# Servorino_FT230X_prototype.net
KiCad netlist of a schematic drawn in EAGLE
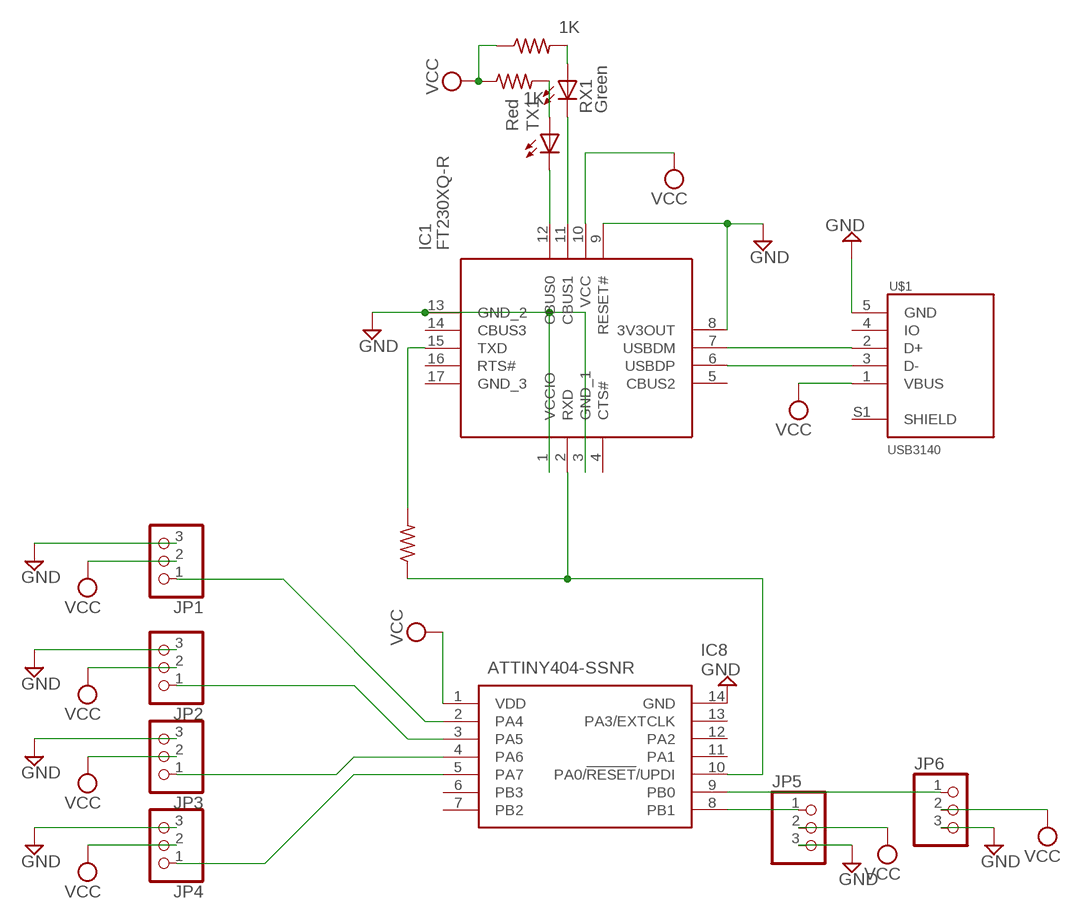
[diagram p0: schematic, sheet 1]

(export (version "E")
  (design (tool "Eeschema 10.0.6"))
  (components
    (comp (ref "IC1")
      (value "FT230XQ-R")
      (footprint "eagle-import:QFN65P400X400X80-17N")
      (fields (field (name "MOUSER_PART_NUMBER") "895-FT230XQ-R"))
      (libsource (lib "eagle-import") (part "FT230XQ-R"))
    )
    (comp (ref "IC8")
      (value "ATTINY404-SSNR")
      (footprint "eagle-import:SOIC127P600X175-14N")
      (fields (field (name "MOUSER_PART_NUMBER") "556-ATTINY404-SSNR"))
      (libsource (lib "eagle-import") (part "ATTINY404-SSNR"))
    )
    (comp (ref "JP1")
      (value "PINHD-1X3")
      (footprint "eagle-import:1X03")
      (libsource (lib "eagle-import") (part "PINHD-1X3"))
    )
    (comp (ref "JP2")
      (value "PINHD-1X3")
      (footprint "eagle-import:1X03")
      (libsource (lib "eagle-import") (part "PINHD-1X3"))
    )
    (comp (ref "JP3")
      (value "PINHD-1X3")
      (footprint "eagle-import:1X03")
      (libsource (lib "eagle-import") (part "PINHD-1X3"))
    )
    (comp (ref "JP4")
      (value "PINHD-1X3")
      (footprint "eagle-import:1X03")
      (libsource (lib "eagle-import") (part "PINHD-1X3"))
    )
    (comp (ref "JP5")
      (value "PINHD-1X3")
      (footprint "eagle-import:1X03")
      (libsource (lib "eagle-import") (part "PINHD-1X3"))
    )
    (comp (ref "JP6")
      (value "PINHD-1X3")
      (footprint "eagle-import:1X03")
      (libsource (lib "eagle-import") (part "PINHD-1X3"))
    )
    (comp (ref "R4")
      (value "1K")
      (footprint "eagle-import:R0805")
      (libsource (lib "eagle-import") (part "R-US_R0805"))
    )
    (comp (ref "R5")
      (value "1K")
      (footprint "eagle-import:R0805")
      (libsource (lib "eagle-import") (part "R-US_R0805"))
    )
    (comp (ref "R6")
      (value "470")
      (footprint "eagle-import:R0805")
      (libsource (lib "eagle-import") (part "R-US_R0805"))
    )
    (comp (ref "RX1")
      (value "Green")
      (footprint "eagle-import:CHIP-LED0805")
      (libsource (lib "eagle-import") (part "LEDCHIP-LED0805"))
    )
    (comp (ref "TX1")
      (value "Red")
      (footprint "eagle-import:CHIP-LED0805")
      (libsource (lib "eagle-import") (part "LEDCHIP-LED0805"))
    )
    (comp (ref "U$1")
      (value "USB3140")
      (footprint "eagle-import:USB3140-30-0170-0-C")
      (libsource (lib "eagle-import") (part "USB3140"))
    )
  )
  (nets
    (net (code "1") (name "GND") (class "Default")
      (node (ref "IC1") (pin "1") (pinfunction "VCCIO_1") (pintype "bidirectional"))
      (node (ref "IC1") (pin "13") (pinfunction "GND_2_13") (pintype "bidirectional"))
      (node (ref "IC1") (pin "3") (pinfunction "GND_1_3") (pintype "bidirectional"))
      (node (ref "IC1") (pin "8") (pinfunction "3V3OUT_8") (pintype "bidirectional"))
      (node (ref "IC1") (pin "9") (pinfunction "RESET#_9") (pintype "bidirectional"))
      (node (ref "IC8") (pin "14") (pinfunction "GND_14") (pintype "bidirectional"))
      (node (ref "JP1") (pin "3") (pinfunction "3_3") (pintype "passive"))
      (node (ref "JP2") (pin "3") (pinfunction "3_3") (pintype "passive"))
      (node (ref "JP3") (pin "3") (pinfunction "3_3") (pintype "passive"))
      (node (ref "JP4") (pin "3") (pinfunction "3_3") (pintype "passive"))
      (node (ref "JP5") (pin "3") (pinfunction "3_3") (pintype "passive"))
      (node (ref "JP6") (pin "3") (pinfunction "3_3") (pintype "passive"))
      (node (ref "U$1") (pin "5") (pinfunction "GND_5") (pintype "passive"))
    )
    (net (code "2") (name "Net-(IC1-CBUS0)") (class "Default")
      (node (ref "IC1") (pin "12") (pinfunction "CBUS0_12") (pintype "bidirectional"))
      (node (ref "TX1") (pin "C") (pinfunction "C_C") (pintype "passive"))
    )
    (net (code "3") (name "Net-(IC1-CBUS1)") (class "Default")
      (node (ref "IC1") (pin "11") (pinfunction "CBUS1_11") (pintype "bidirectional"))
      (node (ref "RX1") (pin "C") (pinfunction "C_C") (pintype "passive"))
    )
    (net (code "4") (name "Net-(IC1-RXD)") (class "Default")
      (node (ref "IC1") (pin "2") (pinfunction "RXD_2") (pintype "bidirectional"))
      (node (ref "IC8") (pin "10") (pinfunction "PA0/~{RESET}/UPDI_10") (pintype "bidirectional"))
      (node (ref "R6") (pin "1") (pinfunction "1_1") (pintype "passive"))
    )
    (net (code "5") (name "Net-(IC1-TXD)") (class "Default")
      (node (ref "IC1") (pin "15") (pinfunction "TXD_15") (pintype "bidirectional"))
      (node (ref "R6") (pin "2") (pinfunction "2_2") (pintype "passive"))
    )
    (net (code "6") (name "Net-(IC1-USBDM)") (class "Default")
      (node (ref "IC1") (pin "7") (pinfunction "USBDM_7") (pintype "bidirectional"))
      (node (ref "U$1") (pin "2") (pinfunction "D+_2") (pintype "passive"))
    )
    (net (code "7") (name "Net-(IC1-USBDP)") (class "Default")
      (node (ref "IC1") (pin "6") (pinfunction "USBDP_6") (pintype "bidirectional"))
      (node (ref "U$1") (pin "3") (pinfunction "D-_3") (pintype "passive"))
    )
    (net (code "8") (name "Net-(IC8-PA4)") (class "Default")
      (node (ref "IC8") (pin "2") (pinfunction "PA4_2") (pintype "bidirectional"))
      (node (ref "JP1") (pin "1") (pinfunction "1_1") (pintype "passive"))
    )
    (net (code "9") (name "Net-(IC8-PA5)") (class "Default")
      (node (ref "IC8") (pin "3") (pinfunction "PA5_3") (pintype "bidirectional"))
      (node (ref "JP2") (pin "1") (pinfunction "1_1") (pintype "passive"))
    )
    (net (code "10") (name "Net-(IC8-PA6)") (class "Default")
      (node (ref "IC8") (pin "4") (pinfunction "PA6_4") (pintype "bidirectional"))
      (node (ref "JP3") (pin "1") (pinfunction "1_1") (pintype "passive"))
    )
    (net (code "11") (name "Net-(IC8-PA7)") (class "Default")
      (node (ref "IC8") (pin "5") (pinfunction "PA7_5") (pintype "bidirectional"))
      (node (ref "JP4") (pin "1") (pinfunction "1_1") (pintype "passive"))
    )
    (net (code "12") (name "Net-(IC8-PB0)") (class "Default")
      (node (ref "IC8") (pin "9") (pinfunction "PB0_9") (pintype "bidirectional"))
      (node (ref "JP6") (pin "1") (pinfunction "1_1") (pintype "passive"))
    )
    (net (code "13") (name "Net-(IC8-PB1)") (class "Default")
      (node (ref "IC8") (pin "8") (pinfunction "PB1_8") (pintype "bidirectional"))
      (node (ref "JP5") (pin "1") (pinfunction "1_1") (pintype "passive"))
    )
    (net (code "14") (name "Net-(R4-Pad2)") (class "Default")
      (node (ref "R4") (pin "2") (pinfunction "2_2") (pintype "passive"))
      (node (ref "RX1") (pin "A") (pinfunction "A_A") (pintype "passive"))
    )
    (net (code "15") (name "Net-(R5-Pad2)") (class "Default")
      (node (ref "R5") (pin "2") (pinfunction "2_2") (pintype "passive"))
      (node (ref "TX1") (pin "A") (pinfunction "A_A") (pintype "passive"))
    )
    (net (code "16") (name "VCC") (class "Default")
      (node (ref "IC1") (pin "10") (pinfunction "VCC_10") (pintype "bidirectional"))
      (node (ref "IC8") (pin "1") (pinfunction "VDD_1") (pintype "bidirectional"))
      (node (ref "JP1") (pin "2") (pinfunction "2_2") (pintype "passive"))
      (node (ref "JP2") (pin "2") (pinfunction "2_2") (pintype "passive"))
      (node (ref "JP3") (pin "2") (pinfunction "2_2") (pintype "passive"))
      (node (ref "JP4") (pin "2") (pinfunction "2_2") (pintype "passive"))
      (node (ref "JP5") (pin "2") (pinfunction "2_2") (pintype "passive"))
      (node (ref "JP6") (pin "2") (pinfunction "2_2") (pintype "passive"))
      (node (ref "R4") (pin "1") (pinfunction "1_1") (pintype "passive"))
      (node (ref "R5") (pin "1") (pinfunction "1_1") (pintype "passive"))
      (node (ref "U$1") (pin "1") (pinfunction "VBUS_1") (pintype "passive"))
    )
    (net (code "17") (name "unconnected-(IC1-CBUS2-Pad5)") (class "Default")
      (node (ref "IC1") (pin "5") (pinfunction "CBUS2_5") (pintype "bidirectional"))
    )
    (net (code "18") (name "unconnected-(IC1-CBUS3-Pad14)") (class "Default")
      (node (ref "IC1") (pin "14") (pinfunction "CBUS3_14") (pintype "bidirectional"))
    )
    (net (code "19") (name "unconnected-(IC1-CTS#-Pad4)") (class "Default")
      (node (ref "IC1") (pin "4") (pinfunction "CTS#_4") (pintype "bidirectional"))
    )
    (net (code "20") (name "unconnected-(IC1-GND_3-Pad17)") (class "Default")
      (node (ref "IC1") (pin "17") (pinfunction "GND_3_17") (pintype "bidirectional"))
    )
    (net (code "21") (name "unconnected-(IC1-RTS#-Pad16)") (class "Default")
      (node (ref "IC1") (pin "16") (pinfunction "RTS#_16") (pintype "bidirectional"))
    )
    (net (code "22") (name "unconnected-(IC8-PA1-Pad11)") (class "Default")
      (node (ref "IC8") (pin "11") (pinfunction "PA1_11") (pintype "bidirectional"))
    )
    (net (code "23") (name "unconnected-(IC8-PA2-Pad12)") (class "Default")
      (node (ref "IC8") (pin "12") (pinfunction "PA2_12") (pintype "bidirectional"))
    )
    (net (code "24") (name "unconnected-(IC8-PA3{slash}EXTCLK-Pad13)") (class "Default")
      (node (ref "IC8") (pin "13") (pinfunction "PA3/EXTCLK_13") (pintype "bidirectional"))
    )
    (net (code "25") (name "unconnected-(IC8-PB2-Pad7)") (class "Default")
      (node (ref "IC8") (pin "7") (pinfunction "PB2_7") (pintype "bidirectional"))
    )
    (net (code "26") (name "unconnected-(IC8-PB3-Pad6)") (class "Default")
      (node (ref "IC8") (pin "6") (pinfunction "PB3_6") (pintype "bidirectional"))
    )
    (net (code "27") (name "unconnected-(U$1-IO-Pad4)") (class "Default")
      (node (ref "U$1") (pin "4") (pinfunction "IO_4") (pintype "passive"))
    )
    (net (code "28") (name "unconnected-(U$1-SHIELD-PadS1)") (class "Default")
      (node (ref "U$1") (pin "S1") (pinfunction "SHIELD_S1") (pintype "passive"))
    )
  )
)
